# Motor_Interface_-_Thermistors.net
KiCad netlist of a schematic drawn in Altium Designer
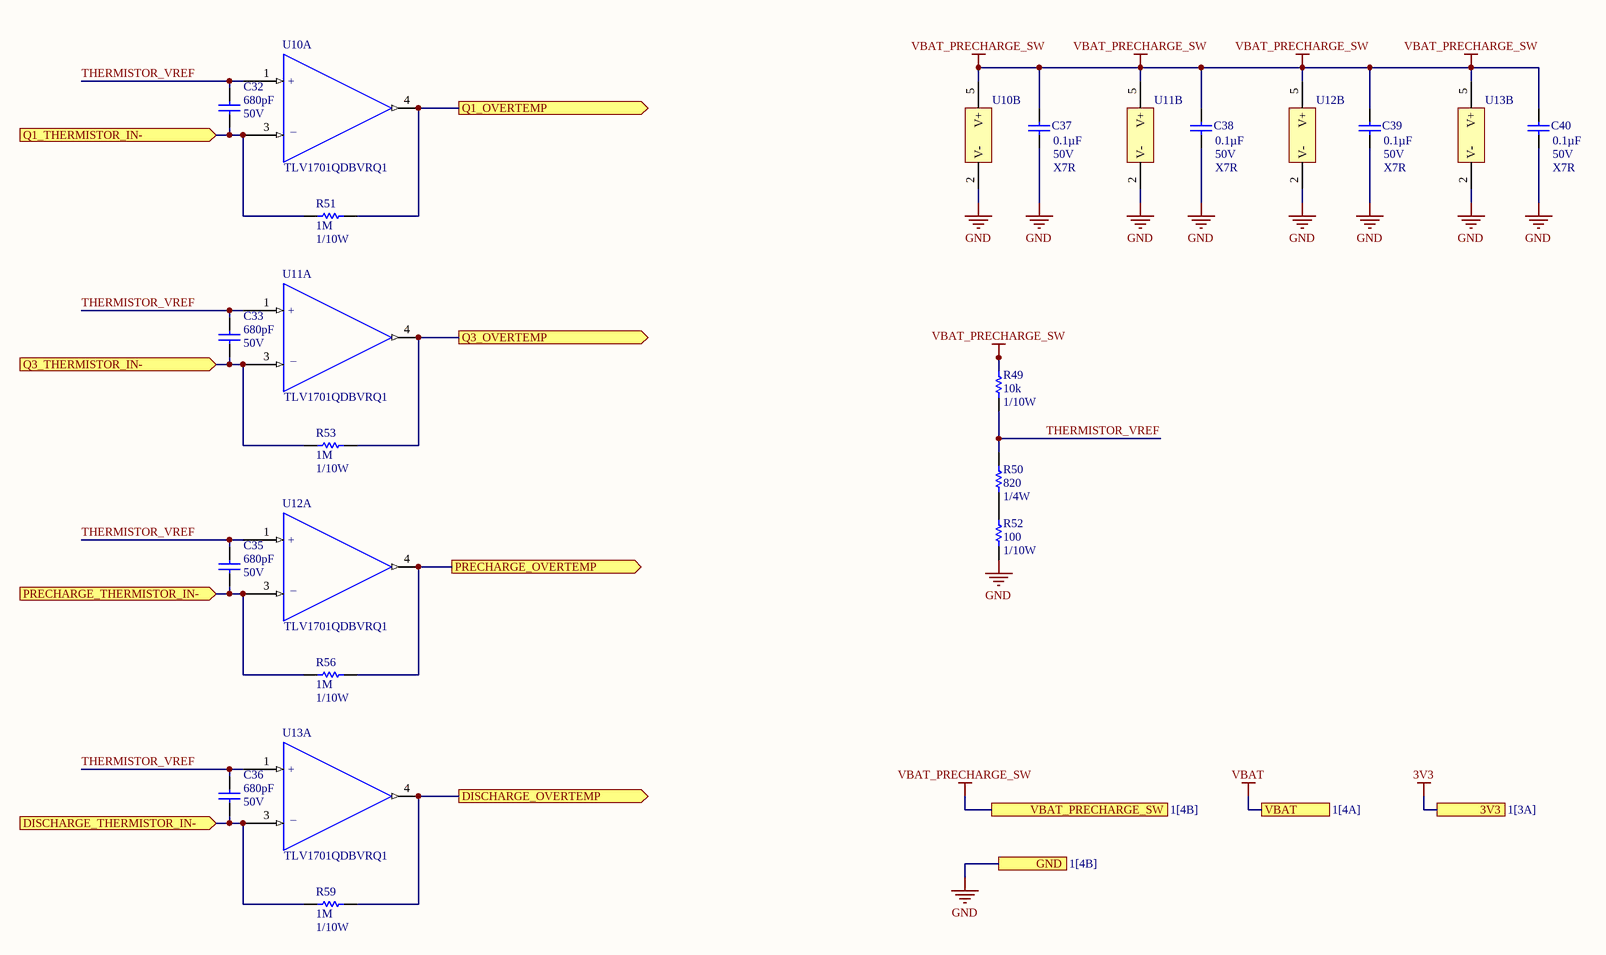
[diagram p0: Motor Interface - Thermistors.SchDoc]

(export (version "E")
  (design (tool "Eeschema 10.0.6"))
  (components
    (comp (ref "C32")
      (value "CAP CER 680PF 50V C0G/NP0 0603")
      (footprint "CAP, 0603")
      (description "680pF ±5% 50V Ceramic Capacitor C0G, NP0 0603 (1608 Metric)")
      (fields
        (field (name "MANUFACTURER") "Samsung")
        (field (name "MANUFACTURER PART NUMBER") "CL10C681JB8NNNC")
        (field (name "VOLTAGE") "50V")
        (field (name "CAPACITANCE") "680pF")
      )
      (libsource (lib "Schematic Diagrams") (part "CAP CER 680PF 50V C0G 0603"))
    )
    (comp (ref "C33")
      (value "CAP CER 680PF 50V C0G/NP0 0603")
      (footprint "CAP, 0603")
      (description "680pF ±5% 50V Ceramic Capacitor C0G, NP0 0603 (1608 Metric)")
      (fields
        (field (name "MANUFACTURER") "Samsung")
        (field (name "MANUFACTURER PART NUMBER") "CL10C681JB8NNNC")
        (field (name "VOLTAGE") "50V")
        (field (name "CAPACITANCE") "680pF")
      )
      (libsource (lib "Schematic Diagrams") (part "CAP CER 680PF 50V C0G 0603"))
    )
    (comp (ref "C35")
      (value "CAP CER 680PF 50V C0G/NP0 0603")
      (footprint "CAP, 0603")
      (description "680pF ±5% 50V Ceramic Capacitor C0G, NP0 0603 (1608 Metric)")
      (fields
        (field (name "MANUFACTURER") "Samsung")
        (field (name "MANUFACTURER PART NUMBER") "CL10C681JB8NNNC")
        (field (name "VOLTAGE") "50V")
        (field (name "CAPACITANCE") "680pF")
      )
      (libsource (lib "Schematic Diagrams") (part "CAP CER 680PF 50V C0G 0603"))
    )
    (comp (ref "C36")
      (value "CAP CER 680PF 50V C0G/NP0 0603")
      (footprint "CAP, 0603")
      (description "680pF ±5% 50V Ceramic Capacitor C0G, NP0 0603 (1608 Metric)")
      (fields
        (field (name "MANUFACTURER") "Samsung")
        (field (name "MANUFACTURER PART NUMBER") "CL10C681JB8NNNC")
        (field (name "VOLTAGE") "50V")
        (field (name "CAPACITANCE") "680pF")
      )
      (libsource (lib "Schematic Diagrams") (part "CAP CER 680PF 50V C0G 0603"))
    )
    (comp (ref "C37")
      (value "CAP CER 0.1UF 50V 10% X7R 0603")
      (footprint "CAP, 0603")
      (description "0.10µF ±10% 50V Ceramic Capacitor X7R 0603 (1608 Metric)")
      (fields
        (field (name "VOLTAGE") "50V")
        (field (name "TOLERANCE") "±10%")
        (field (name "CAPACITANCE") "0.1µF")
        (field (name "TEMPERATURE COEFFICIENT") "X7R")
      )
      (libsource (lib "Schematic Diagrams") (part "CAP CER 0.1UF 50V 10% X7R 0603"))
    )
    (comp (ref "C38")
      (value "CAP CER 0.1UF 50V 10% X7R 0603")
      (footprint "CAP, 0603")
      (description "0.10µF ±10% 50V Ceramic Capacitor X7R 0603 (1608 Metric)")
      (fields
        (field (name "VOLTAGE") "50V")
        (field (name "TOLERANCE") "±10%")
        (field (name "CAPACITANCE") "0.1µF")
        (field (name "TEMPERATURE COEFFICIENT") "X7R")
      )
      (libsource (lib "Schematic Diagrams") (part "CAP CER 0.1UF 50V 10% X7R 0603"))
    )
    (comp (ref "C39")
      (value "CAP CER 0.1UF 50V 10% X7R 0603")
      (footprint "CAP, 0603")
      (description "0.10µF ±10% 50V Ceramic Capacitor X7R 0603 (1608 Metric)")
      (fields
        (field (name "VOLTAGE") "50V")
        (field (name "TOLERANCE") "±10%")
        (field (name "CAPACITANCE") "0.1µF")
        (field (name "TEMPERATURE COEFFICIENT") "X7R")
      )
      (libsource (lib "Schematic Diagrams") (part "CAP CER 0.1UF 50V 10% X7R 0603"))
    )
    (comp (ref "C40")
      (value "CAP CER 0.1UF 50V 10% X7R 0603")
      (footprint "CAP, 0603")
      (description "0.10µF ±10% 50V Ceramic Capacitor X7R 0603 (1608 Metric)")
      (fields
        (field (name "VOLTAGE") "50V")
        (field (name "TOLERANCE") "±10%")
        (field (name "CAPACITANCE") "0.1µF")
        (field (name "TEMPERATURE COEFFICIENT") "X7R")
      )
      (libsource (lib "Schematic Diagrams") (part "CAP CER 0.1UF 50V 10% X7R 0603"))
    )
    (comp (ref "R49")
      (value "RES 10K OHM 1% 1/10W 0603")
      (footprint "RES, 0603")
      (description "RES SMD 10K OHM 1% 1/10W 0603")
      (fields
        (field (name "TOLERANCE") "±1%")
        (field (name "RESISTANCE") "10k")
        (field (name "POWER") "1/10W")
      )
      (libsource (lib "Schematic Diagrams") (part "RES 10K OHM 1% 1/10W 0603"))
    )
    (comp (ref "R50")
      (value "RES 820 OHM 5% 1/4W 0603")
      (footprint "RES, 0603")
      (description "RES SMD 820 OHM 5% 1/4W 0603")
      (fields
        (field (name "TOLERANCE") "±5%")
        (field (name "RESISTANCE") "820")
        (field (name "POWER") "1/4W")
      )
      (libsource (lib "Schematic Diagrams") (part "RES 820 OHM 5% 1/4W 0603"))
    )
    (comp (ref "R51")
      (value "RES 1M OHM 1% 1/10W 0603")
      (footprint "RES, 0603")
      (description "1M Ohm ±1% 0.1W, 1/10W Chip Resistor 0603 (1608 Metric) Moisture Resistant Thick Film")
      (fields
        (field (name "TOLERANCE") "±1%")
        (field (name "RESISTANCE (OHMS)") "1M")
        (field (name "POWER (WATTS)") "1/10W")
      )
      (libsource (lib "Schematic Diagrams") (part "RES 1M OHM 1% 1/10W 0603"))
    )
    (comp (ref "R52")
      (value "RES 100 OHM 1% 1/10W 0603")
      (footprint "RES, 0603")
      (description "100 Ohm ±1% 0.1W, 1/10W Chip Resistor 0603 (1608 Metric) Moisture Resistant Thick Film")
      (fields
        (field (name "TOLERANCE") "±1%")
        (field (name "RESISTANCE") "100")
        (field (name "POWER") "1/10W")
      )
      (libsource (lib "Schematic Diagrams") (part "RES 100 OHM 1% 1/10W 0603"))
    )
    (comp (ref "R53")
      (value "RES 1M OHM 1% 1/10W 0603")
      (footprint "RES, 0603")
      (description "1M Ohm ±1% 0.1W, 1/10W Chip Resistor 0603 (1608 Metric) Moisture Resistant Thick Film")
      (fields
        (field (name "TOLERANCE") "±1%")
        (field (name "RESISTANCE (OHMS)") "1M")
        (field (name "POWER (WATTS)") "1/10W")
      )
      (libsource (lib "Schematic Diagrams") (part "RES 1M OHM 1% 1/10W 0603"))
    )
    (comp (ref "R56")
      (value "RES 1M OHM 1% 1/10W 0603")
      (footprint "RES, 0603")
      (description "1M Ohm ±1% 0.1W, 1/10W Chip Resistor 0603 (1608 Metric) Moisture Resistant Thick Film")
      (fields
        (field (name "TOLERANCE") "±1%")
        (field (name "RESISTANCE (OHMS)") "1M")
        (field (name "POWER (WATTS)") "1/10W")
      )
      (libsource (lib "Schematic Diagrams") (part "RES 1M OHM 1% 1/10W 0603"))
    )
    (comp (ref "R59")
      (value "RES 1M OHM 1% 1/10W 0603")
      (footprint "RES, 0603")
      (description "1M Ohm ±1% 0.1W, 1/10W Chip Resistor 0603 (1608 Metric) Moisture Resistant Thick Film")
      (fields
        (field (name "TOLERANCE") "±1%")
        (field (name "RESISTANCE (OHMS)") "1M")
        (field (name "POWER (WATTS)") "1/10W")
      )
      (libsource (lib "Schematic Diagrams") (part "RES 1M OHM 1% 1/10W 0603"))
    )
    (comp (ref "U10")
      (value "IC COMPARATOR TLV1701 SOT-23-5")
      (footprint "SOT95P280X145-5N")
      (description "Comparator General Purpose Open Collector SOT-23-5")
      (fields
        (field (name "MANUFACTURER") "Texas Instruments")
        (field (name "MANUFACTURER PART NUMBER") "TLV1701QDBVRQ1")
      )
      (libsource (lib "Schematic Diagrams") (part "IC COMPARATOR TLV1701 SOT-23-5"))
    )
    (comp (ref "U11")
      (value "IC COMPARATOR TLV1701 SOT-23-5")
      (footprint "SOT95P280X145-5N")
      (description "Comparator General Purpose Open Collector SOT-23-5")
      (fields
        (field (name "MANUFACTURER") "Texas Instruments")
        (field (name "MANUFACTURER PART NUMBER") "TLV1701QDBVRQ1")
      )
      (libsource (lib "Schematic Diagrams") (part "IC COMPARATOR TLV1701 SOT-23-5"))
    )
    (comp (ref "U12")
      (value "IC COMPARATOR TLV1701 SOT-23-5")
      (footprint "SOT95P280X145-5N")
      (description "Comparator General Purpose Open Collector SOT-23-5")
      (fields
        (field (name "MANUFACTURER") "Texas Instruments")
        (field (name "MANUFACTURER PART NUMBER") "TLV1701QDBVRQ1")
      )
      (libsource (lib "Schematic Diagrams") (part "IC COMPARATOR TLV1701 SOT-23-5"))
    )
    (comp (ref "U13")
      (value "IC COMPARATOR TLV1701 SOT-23-5")
      (footprint "SOT95P280X145-5N")
      (description "Comparator General Purpose Open Collector SOT-23-5")
      (fields
        (field (name "MANUFACTURER") "Texas Instruments")
        (field (name "MANUFACTURER PART NUMBER") "TLV1701QDBVRQ1")
      )
      (libsource (lib "Schematic Diagrams") (part "IC COMPARATOR TLV1701 SOT-23-5"))
    )
  )
  (nets
    (net (code "1") (name "/DISCHARGE_OVERTEMP") (class "Default")
      (node (ref "R59") (pin "2") (pinfunction "2_2") (pintype "passive"))
      (node (ref "U13") (pin "4") (pinfunction "OUT_4") (pintype "output"))
    )
    (net (code "2") (name "/DISCHARGE_THERMISTOR_IN-") (class "Default")
      (node (ref "C36") (pin "2") (pinfunction "2_2") (pintype "passive"))
      (node (ref "R59") (pin "1") (pinfunction "1_1") (pintype "passive"))
      (node (ref "U13") (pin "3") (pinfunction "-IN_3") (pintype "input"))
    )
    (net (code "3") (name "/PRECHARGE_OVERTEMP") (class "Default")
      (node (ref "R56") (pin "2") (pinfunction "2_2") (pintype "passive"))
      (node (ref "U12") (pin "4") (pinfunction "OUT_4") (pintype "output"))
    )
    (net (code "4") (name "/PRECHARGE_THERMISTOR_IN-") (class "Default")
      (node (ref "C35") (pin "2") (pinfunction "2_2") (pintype "passive"))
      (node (ref "R56") (pin "1") (pinfunction "1_1") (pintype "passive"))
      (node (ref "U12") (pin "3") (pinfunction "-IN_3") (pintype "input"))
    )
    (net (code "5") (name "/Q1_OVERTEMP") (class "Default")
      (node (ref "R51") (pin "2") (pinfunction "2_2") (pintype "passive"))
      (node (ref "U10") (pin "4") (pinfunction "OUT_4") (pintype "output"))
    )
    (net (code "6") (name "/Q1_THERMISTOR_IN-") (class "Default")
      (node (ref "C32") (pin "2") (pinfunction "2_2") (pintype "passive"))
      (node (ref "R51") (pin "1") (pinfunction "1_1") (pintype "passive"))
      (node (ref "U10") (pin "3") (pinfunction "-IN_3") (pintype "input"))
    )
    (net (code "7") (name "/Q3_OVERTEMP") (class "Default")
      (node (ref "R53") (pin "2") (pinfunction "2_2") (pintype "passive"))
      (node (ref "U11") (pin "4") (pinfunction "OUT_4") (pintype "output"))
    )
    (net (code "8") (name "/Q3_THERMISTOR_IN-") (class "Default")
      (node (ref "C33") (pin "2") (pinfunction "2_2") (pintype "passive"))
      (node (ref "R53") (pin "1") (pinfunction "1_1") (pintype "passive"))
      (node (ref "U11") (pin "3") (pinfunction "-IN_3") (pintype "input"))
    )
    (net (code "9") (name "/THERMISTOR_VREF") (class "Default")
      (node (ref "C32") (pin "1") (pinfunction "1_1") (pintype "passive"))
      (node (ref "C33") (pin "1") (pinfunction "1_1") (pintype "passive"))
      (node (ref "C35") (pin "1") (pinfunction "1_1") (pintype "passive"))
      (node (ref "C36") (pin "1") (pinfunction "1_1") (pintype "passive"))
      (node (ref "R49") (pin "2") (pinfunction "2_2") (pintype "passive"))
      (node (ref "R50") (pin "1") (pinfunction "1_1") (pintype "passive"))
      (node (ref "U10") (pin "1") (pinfunction "+IN_1") (pintype "input"))
      (node (ref "U11") (pin "1") (pinfunction "+IN_1") (pintype "input"))
      (node (ref "U12") (pin "1") (pinfunction "+IN_1") (pintype "input"))
      (node (ref "U13") (pin "1") (pinfunction "+IN_1") (pintype "input"))
    )
    (net (code "11") (name "GND") (class "Default")
      (node (ref "C37") (pin "1") (pinfunction "1_1") (pintype "passive"))
      (node (ref "C38") (pin "1") (pinfunction "1_1") (pintype "passive"))
      (node (ref "C39") (pin "1") (pinfunction "1_1") (pintype "passive"))
      (node (ref "C40") (pin "1") (pinfunction "1_1") (pintype "passive"))
      (node (ref "R52") (pin "2") (pinfunction "2_2") (pintype "passive"))
      (node (ref "U10") (pin "2") (pinfunction "V-_2") (pintype "power_in"))
      (node (ref "U11") (pin "2") (pinfunction "V-_2") (pintype "power_in"))
      (node (ref "U12") (pin "2") (pinfunction "V-_2") (pintype "power_in"))
      (node (ref "U13") (pin "2") (pinfunction "V-_2") (pintype "power_in"))
    )
    (net (code "12") (name "Net-(R50-Pad2)") (class "Default")
      (node (ref "R50") (pin "2") (pinfunction "2_2") (pintype "passive"))
      (node (ref "R52") (pin "1") (pinfunction "1_1") (pintype "passive"))
    )
    (net (code "14") (name "VBAT_PRECHARGE_SW") (class "Default")
      (node (ref "C37") (pin "2") (pinfunction "2_2") (pintype "passive"))
      (node (ref "C38") (pin "2") (pinfunction "2_2") (pintype "passive"))
      (node (ref "C39") (pin "2") (pinfunction "2_2") (pintype "passive"))
      (node (ref "C40") (pin "2") (pinfunction "2_2") (pintype "passive"))
      (node (ref "R49") (pin "1") (pinfunction "1_1") (pintype "passive"))
      (node (ref "U10") (pin "5") (pinfunction "V+_5") (pintype "power_in"))
      (node (ref "U11") (pin "5") (pinfunction "V+_5") (pintype "power_in"))
      (node (ref "U12") (pin "5") (pinfunction "V+_5") (pintype "power_in"))
      (node (ref "U13") (pin "5") (pinfunction "V+_5") (pintype "power_in"))
    )
  )
)
